# Dash_LEDs.net
KiCad netlist of a schematic drawn in EAGLE
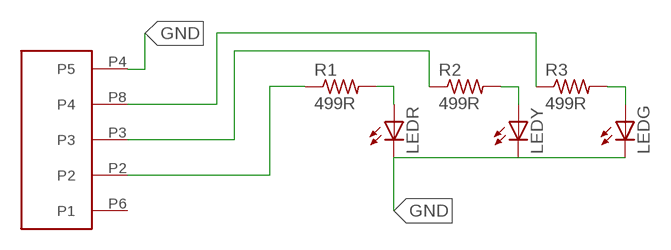
[diagram p0: schematic, sheet 1]

(export (version "E")
  (design (tool "Eeschema 10.0.6"))
  (components
    (comp (ref "LEDG")
      (value "LED5MM")
      (footprint "eagle-import:LED5MM")
      (libsource (lib "eagle-import") (part "LED5MM"))
    )
    (comp (ref "LEDR")
      (value "LED5MM")
      (footprint "eagle-import:LED5MM")
      (libsource (lib "eagle-import") (part "LED5MM"))
    )
    (comp (ref "LEDY")
      (value "LED5MM")
      (footprint "eagle-import:LED5MM")
      (libsource (lib "eagle-import") (part "LED5MM"))
    )
    (comp (ref "R1")
      (value "499R")
      (footprint "eagle-import:R0805")
      (libsource (lib "eagle-import") (part "R-US_R0805"))
    )
    (comp (ref "R2")
      (value "499R")
      (footprint "eagle-import:R0805")
      (libsource (lib "eagle-import") (part "R-US_R0805"))
    )
    (comp (ref "R3")
      (value "499R")
      (footprint "eagle-import:R0805")
      (libsource (lib "eagle-import") (part "R-US_R0805"))
    )
    (comp (ref "U$1")
      (value "PICOLOCK")
      (footprint "eagle-import:PICOLOCK")
      (libsource (lib "eagle-import") (part "PICOLOCK"))
    )
  )
  (nets
    (net (code "1") (name "GND") (class "Default")
      (node (ref "LEDG") (pin "K") (pinfunction "C_K") (pintype "passive"))
      (node (ref "LEDR") (pin "K") (pinfunction "C_K") (pintype "passive"))
      (node (ref "LEDY") (pin "K") (pinfunction "C_K") (pintype "passive"))
      (node (ref "U$1") (pin "P4") (pinfunction "P5_P4") (pintype "bidirectional"))
    )
    (net (code "2") (name "Net-(LEDG-PadA)") (class "Default")
      (node (ref "LEDG") (pin "A") (pinfunction "A_A") (pintype "passive"))
      (node (ref "R3") (pin "2") (pinfunction "2_2") (pintype "passive"))
    )
    (net (code "3") (name "Net-(LEDR-PadA)") (class "Default")
      (node (ref "LEDR") (pin "A") (pinfunction "A_A") (pintype "passive"))
      (node (ref "R1") (pin "2") (pinfunction "2_2") (pintype "passive"))
    )
    (net (code "4") (name "Net-(LEDY-PadA)") (class "Default")
      (node (ref "LEDY") (pin "A") (pinfunction "A_A") (pintype "passive"))
      (node (ref "R2") (pin "2") (pinfunction "2_2") (pintype "passive"))
    )
    (net (code "5") (name "Net-(R1-Pad1)") (class "Default")
      (node (ref "R1") (pin "1") (pinfunction "1_1") (pintype "passive"))
      (node (ref "U$1") (pin "P2") (pinfunction "P2_P2") (pintype "bidirectional"))
    )
    (net (code "6") (name "Net-(R2-Pad1)") (class "Default")
      (node (ref "R2") (pin "1") (pinfunction "1_1") (pintype "passive"))
      (node (ref "U$1") (pin "P3") (pinfunction "P3_P3") (pintype "bidirectional"))
    )
    (net (code "7") (name "Net-(U$1-P4)") (class "Default")
      (node (ref "R3") (pin "1") (pinfunction "1_1") (pintype "passive"))
      (node (ref "U$1") (pin "P8") (pinfunction "P4_P8") (pintype "bidirectional"))
    )
    (net (code "8") (name "unconnected-(U$1-P1-PadP6)") (class "Default")
      (node (ref "U$1") (pin "P6") (pinfunction "P1_P6") (pintype "bidirectional"))
    )
  )
)
